# scanline.net
KiCad netlist of a schematic drawn in Altium Designer
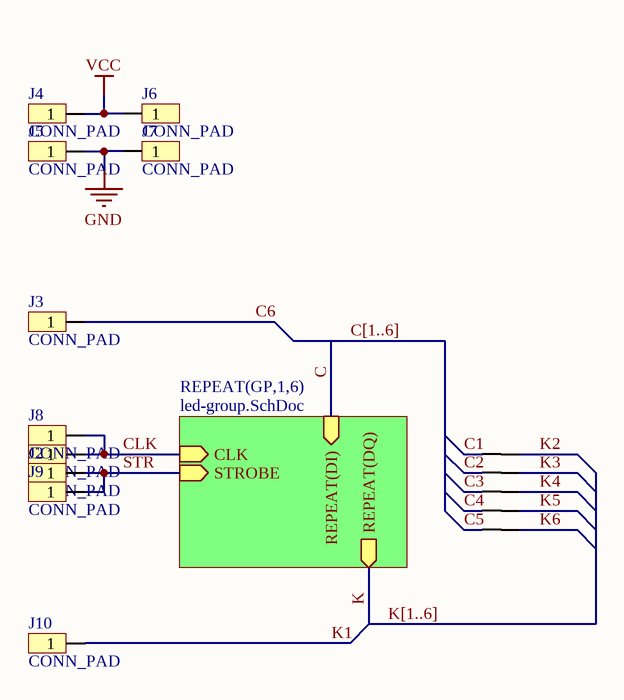
[diagram p0: scanline.SchDoc]

(export (version "E")
  (design (tool "Eeschema 10.0.6"))
  (components
    (comp (ref "J1") (value "CONN_PAD") (libsource (lib "Components") (part "CONN_PAD")))
    (comp (ref "J2") (value "CONN_PAD") (libsource (lib "Components") (part "CONN_PAD")))
    (comp (ref "J3") (value "CONN_PAD") (libsource (lib "Components") (part "CONN_PAD")))
    (comp (ref "J4") (value "CONN_PAD") (libsource (lib "Components") (part "CONN_PAD")))
    (comp (ref "J5") (value "CONN_PAD") (libsource (lib "Components") (part "CONN_PAD")))
    (comp (ref "J6") (value "CONN_PAD") (libsource (lib "") (part "CONN_PAD_1")))
    (comp (ref "J7") (value "CONN_PAD") (libsource (lib "") (part "CONN_PAD_1")))
    (comp (ref "J8") (value "CONN_PAD") (libsource (lib "Components") (part "CONN_PAD")))
    (comp (ref "J9") (value "CONN_PAD") (libsource (lib "Components") (part "CONN_PAD")))
    (comp (ref "J10") (value "CONN_PAD") (libsource (lib "Components") (part "CONN_PAD")))
    (comp (ref "T2") (value "NETTIE") (footprint "NETTIE") (libsource (lib "Components") (part "NETTIE")))
    (comp (ref "T3") (value "NETTIE") (footprint "NETTIE") (libsource (lib "Components") (part "NETTIE")))
    (comp (ref "T4") (value "NETTIE") (footprint "NETTIE") (libsource (lib "Components") (part "NETTIE")))
    (comp (ref "T5") (value "NETTIE") (footprint "NETTIE") (libsource (lib "Components") (part "NETTIE")))
    (comp (ref "T6") (value "NETTIE") (footprint "NETTIE") (libsource (lib "Components") (part "NETTIE")))
  )
  (nets
    (net (code "2") (name "/C1") (class "Default")
      (node (ref "T2") (pin "1") (pinfunction "1_1") (pintype "bidirectional"))
    )
    (net (code "3") (name "/C2") (class "Default")
      (node (ref "T3") (pin "1") (pinfunction "1_1") (pintype "bidirectional"))
    )
    (net (code "4") (name "/C3") (class "Default")
      (node (ref "T4") (pin "1") (pinfunction "1_1") (pintype "bidirectional"))
    )
    (net (code "5") (name "/C4") (class "Default")
      (node (ref "T5") (pin "1") (pinfunction "1_1") (pintype "bidirectional"))
    )
    (net (code "6") (name "/C5") (class "Default")
      (node (ref "T6") (pin "1") (pinfunction "1_1") (pintype "bidirectional"))
    )
    (net (code "7") (name "/C6") (class "Default")
      (node (ref "J3") (pin "1") (pinfunction "1_1") (pintype "passive"))
    )
    (net (code "8") (name "/CLK") (class "Default")
      (node (ref "J1") (pin "1") (pinfunction "1_1") (pintype "passive"))
      (node (ref "J8") (pin "1") (pinfunction "1_1") (pintype "passive"))
    )
    (net (code "11") (name "/K1") (class "Default")
      (node (ref "J10") (pin "1") (pinfunction "1_1") (pintype "passive"))
    )
    (net (code "12") (name "/K2") (class "Default")
      (node (ref "T2") (pin "2") (pinfunction "2_2") (pintype "bidirectional"))
    )
    (net (code "13") (name "/K3") (class "Default")
      (node (ref "T3") (pin "2") (pinfunction "2_2") (pintype "bidirectional"))
    )
    (net (code "14") (name "/K4") (class "Default")
      (node (ref "T4") (pin "2") (pinfunction "2_2") (pintype "bidirectional"))
    )
    (net (code "15") (name "/K5") (class "Default")
      (node (ref "T5") (pin "2") (pinfunction "2_2") (pintype "bidirectional"))
    )
    (net (code "16") (name "/K6") (class "Default")
      (node (ref "T6") (pin "2") (pinfunction "2_2") (pintype "bidirectional"))
    )
    (net (code "18") (name "/STR") (class "Default")
      (node (ref "J2") (pin "1") (pinfunction "1_1") (pintype "passive"))
      (node (ref "J9") (pin "1") (pinfunction "1_1") (pintype "passive"))
    )
    (net (code "19") (name "GND") (class "Default")
      (node (ref "J5") (pin "1") (pinfunction "1_1") (pintype "passive"))
      (node (ref "J7") (pin "1") (pinfunction "1_1") (pintype "passive"))
    )
    (net (code "20") (name "VCC") (class "Default")
      (node (ref "J4") (pin "1") (pinfunction "1_1") (pintype "passive"))
      (node (ref "J6") (pin "1") (pinfunction "1_1") (pintype "passive"))
    )
  )
)
